# arm-mini-pro.net
KiCad netlist of a schematic drawn in EAGLE
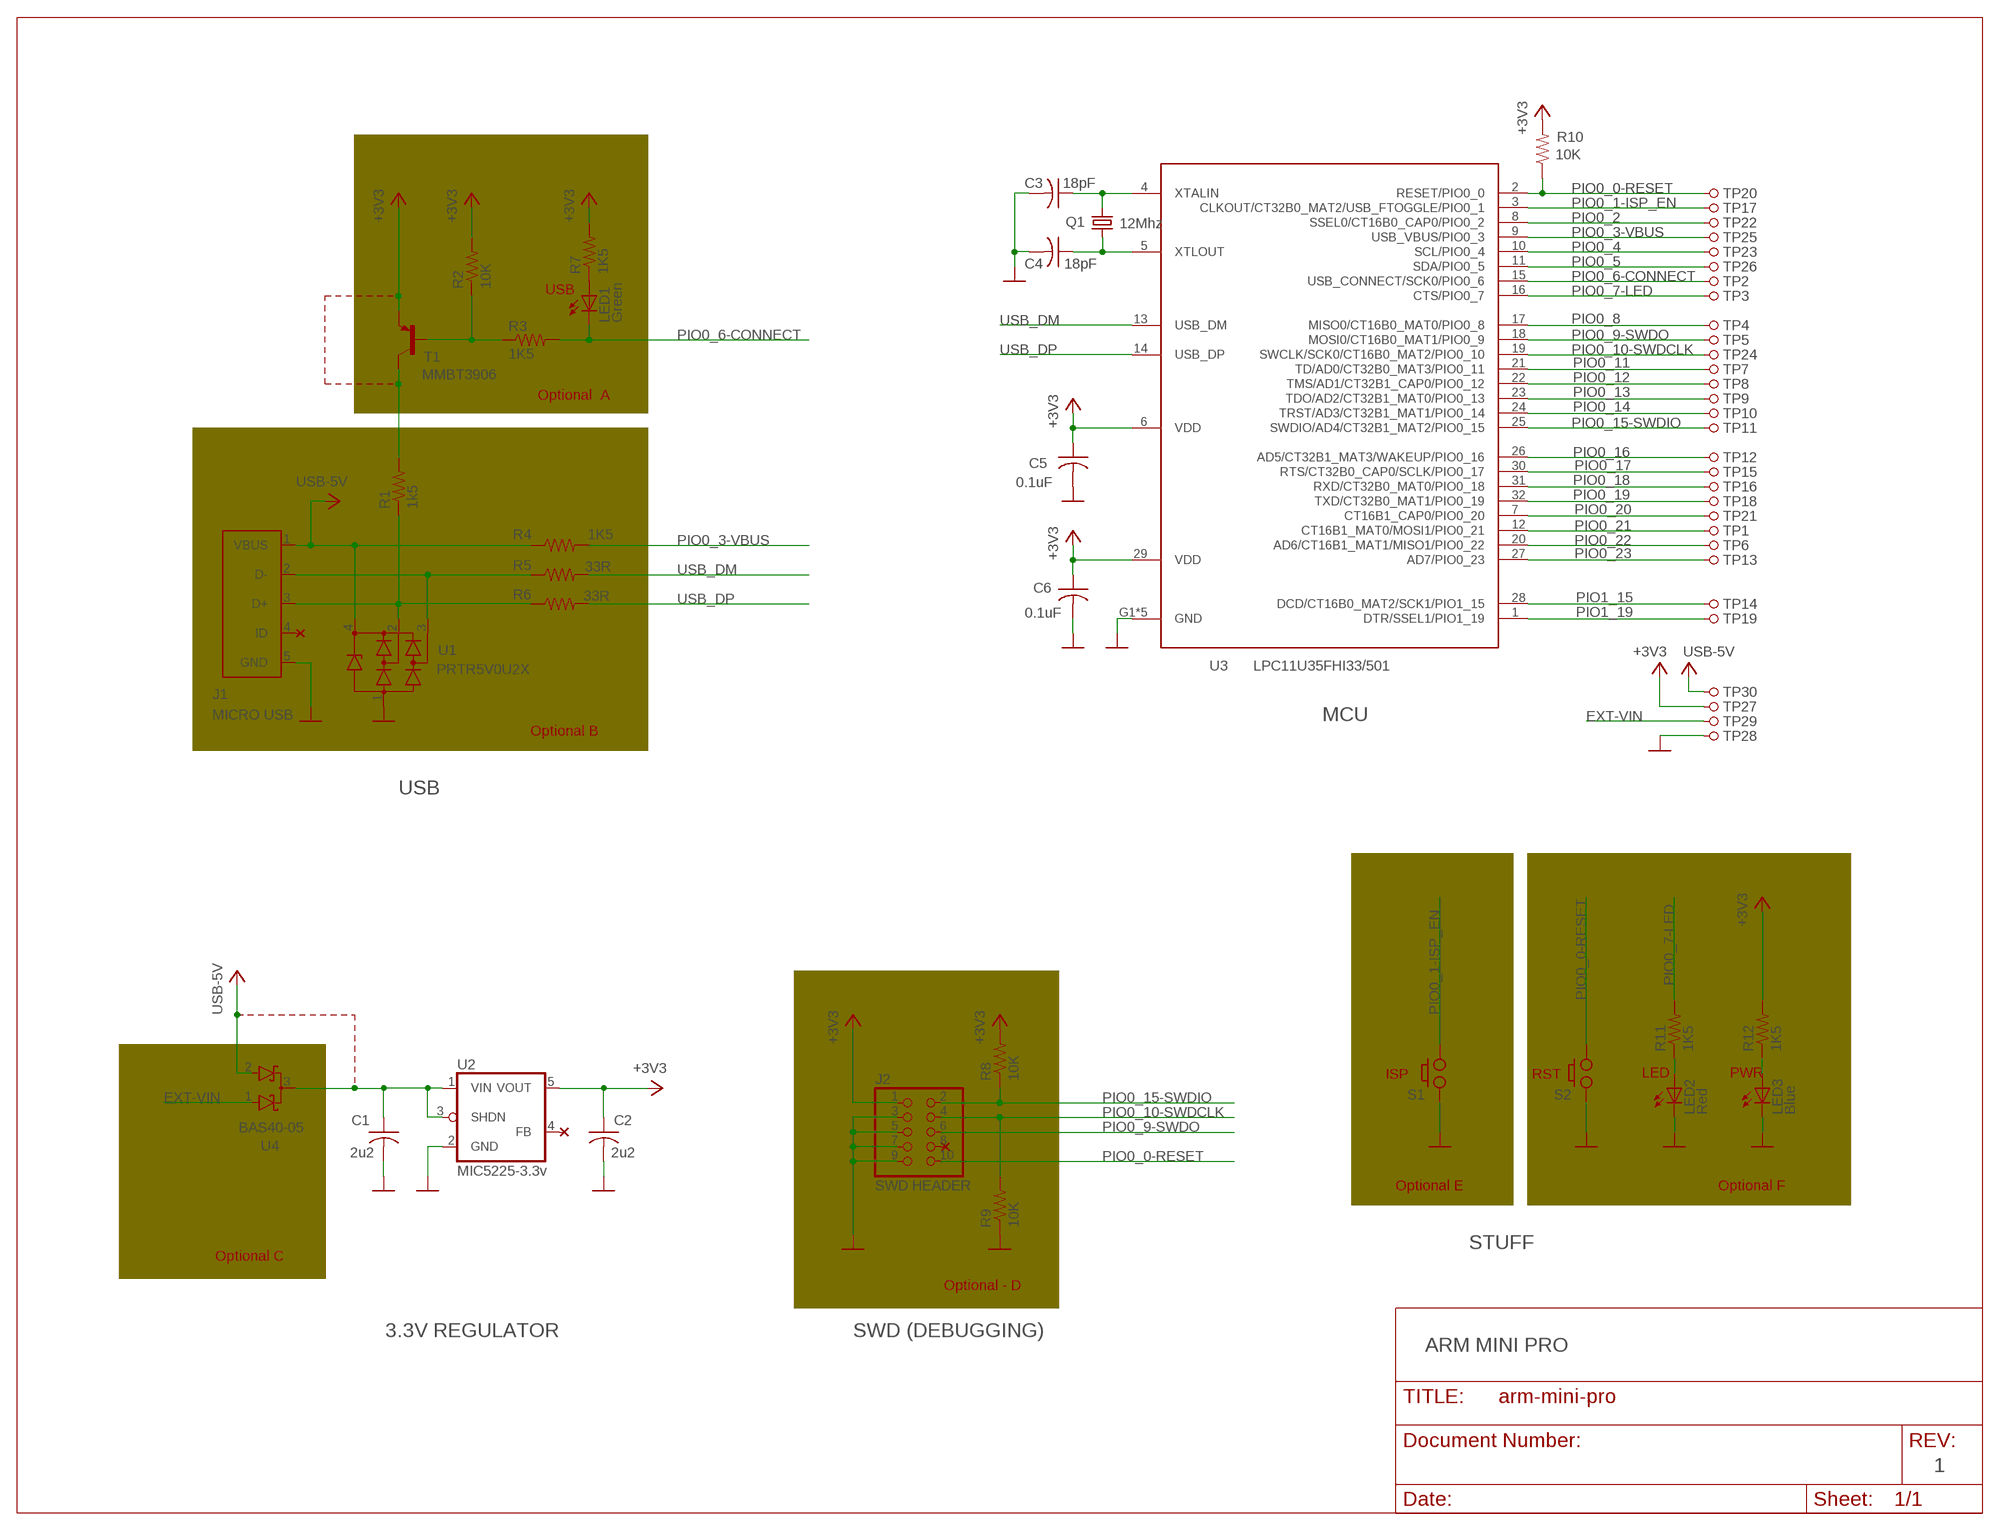
[diagram p0: schematic, sheet 1]

(export (version "E")
  (design (tool "Eeschema 10.0.6"))
  (components
    (comp (ref "C1")
      (value "2u2")
      (footprint "eagle-import:C0603K")
      (libsource (lib "eagle-import") (part "CAPACITORC0603K"))
    )
    (comp (ref "C2")
      (value "2u2")
      (footprint "eagle-import:C0603K")
      (libsource (lib "eagle-import") (part "CAPACITORC0603K"))
    )
    (comp (ref "C3")
      (value "18pF")
      (footprint "eagle-import:C0402K")
      (libsource (lib "eagle-import") (part "C-USC0402K"))
    )
    (comp (ref "C4")
      (value "18pF")
      (footprint "eagle-import:C0402K")
      (libsource (lib "eagle-import") (part "C-USC0402K"))
    )
    (comp (ref "C5")
      (value "0.1uF")
      (footprint "eagle-import:C0603K")
      (libsource (lib "eagle-import") (part "CAPACITORC0603K"))
    )
    (comp (ref "C6")
      (value "0.1uF")
      (footprint "eagle-import:C0603K")
      (libsource (lib "eagle-import") (part "CAPACITORC0603K"))
    )
    (comp (ref "J1")
      (value "MICRO USB")
      (footprint "eagle-import:USB-MICRO-ZX62RD-AB-5P8")
      (libsource (lib "eagle-import") (part "USB"))
    )
    (comp (ref "J2")
      (value "SWD HEADER")
      (footprint "eagle-import:SWD-HEADER")
      (libsource (lib "eagle-import") (part "SWD-HEADER"))
    )
    (comp (ref "LED1")
      (value "Green")
      (footprint "eagle-import:CHIP-LED0603")
      (libsource (lib "eagle-import") (part "LEDCHIP-LED0603"))
    )
    (comp (ref "LED2")
      (value "Red")
      (footprint "eagle-import:CHIP-LED0603")
      (libsource (lib "eagle-import") (part "LEDCHIP-LED0603"))
    )
    (comp (ref "LED3")
      (value "Blue")
      (footprint "eagle-import:CHIP-LED0603")
      (libsource (lib "eagle-import") (part "LEDCHIP-LED0603"))
    )
    (comp (ref "Q1")
      (value "12Mhz")
      (footprint "eagle-import:CRYSTAL")
      (libsource (lib "eagle-import") (part "CRYSTALCTS406"))
    )
    (comp (ref "R1")
      (value "1k5")
      (footprint "eagle-import:R0402")
      (libsource (lib "eagle-import") (part "R-US_R0402"))
    )
    (comp (ref "R2")
      (value "10K")
      (footprint "eagle-import:R0402")
      (libsource (lib "eagle-import") (part "R-US_R0402"))
    )
    (comp (ref "R3")
      (value "1K5")
      (footprint "eagle-import:R0402")
      (libsource (lib "eagle-import") (part "R-US_R0402"))
    )
    (comp (ref "R4")
      (value "1K5")
      (footprint "eagle-import:R0402")
      (libsource (lib "eagle-import") (part "R-US_R0402"))
    )
    (comp (ref "R5")
      (value "33R")
      (footprint "eagle-import:R0402")
      (libsource (lib "eagle-import") (part "R-US_R0402"))
    )
    (comp (ref "R6")
      (value "33R")
      (footprint "eagle-import:R0402")
      (libsource (lib "eagle-import") (part "R-US_R0402"))
    )
    (comp (ref "R7")
      (value "1K5")
      (footprint "eagle-import:R0402")
      (libsource (lib "eagle-import") (part "R-US_R0402"))
    )
    (comp (ref "R8")
      (value "10K")
      (footprint "eagle-import:R0402")
      (libsource (lib "eagle-import") (part "R-US_R0402"))
    )
    (comp (ref "R9")
      (value "10K")
      (footprint "eagle-import:R0402")
      (libsource (lib "eagle-import") (part "R-US_R0402"))
    )
    (comp (ref "R10")
      (value "10K")
      (footprint "eagle-import:R0402")
      (libsource (lib "eagle-import") (part "R-US_R0402"))
    )
    (comp (ref "R11")
      (value "1K5")
      (footprint "eagle-import:R0402")
      (libsource (lib "eagle-import") (part "R-US_R0402"))
    )
    (comp (ref "R12")
      (value "1K5")
      (footprint "eagle-import:R0402")
      (libsource (lib "eagle-import") (part "R-US_R0402"))
    )
    (comp (ref "S1")
      (value "PUSH_BUTTON")
      (footprint "eagle-import:PUSH_BUTTON")
      (libsource (lib "eagle-import") (part "PUSH_BUTTON"))
    )
    (comp (ref "S2")
      (value "PUSH_BUTTON")
      (footprint "eagle-import:PUSH_BUTTON")
      (libsource (lib "eagle-import") (part "PUSH_BUTTON"))
    )
    (comp (ref "T1")
      (value "MMBT3906")
      (footprint "eagle-import:SOT23-BEC")
      (libsource (lib "eagle-import") (part "-PNP-SOT23-BECBC857B"))
    )
    (comp (ref "TP1")
      (value "HDR1")
      (footprint "eagle-import:1X01-SQUARE")
      (libsource (lib "eagle-import") (part "PINHD-1X1SQUARE"))
    )
    (comp (ref "TP2")
      (value "HDR1")
      (footprint "eagle-import:1X01")
      (libsource (lib "eagle-import") (part "PINHD-1X1"))
    )
    (comp (ref "TP3")
      (value "HDR1")
      (footprint "eagle-import:1X01")
      (libsource (lib "eagle-import") (part "PINHD-1X1"))
    )
    (comp (ref "TP4")
      (value "HDR1")
      (footprint "eagle-import:1X01")
      (libsource (lib "eagle-import") (part "PINHD-1X1"))
    )
    (comp (ref "TP5")
      (value "HDR1")
      (footprint "eagle-import:1X01")
      (libsource (lib "eagle-import") (part "PINHD-1X1"))
    )
    (comp (ref "TP6")
      (value "HDR1")
      (footprint "eagle-import:1X01")
      (libsource (lib "eagle-import") (part "PINHD-1X1"))
    )
    (comp (ref "TP7")
      (value "HDR1")
      (footprint "eagle-import:1X01")
      (libsource (lib "eagle-import") (part "PINHD-1X1"))
    )
    (comp (ref "TP8")
      (value "HDR1")
      (footprint "eagle-import:1X01")
      (libsource (lib "eagle-import") (part "PINHD-1X1"))
    )
    (comp (ref "TP9")
      (value "HDR1")
      (footprint "eagle-import:1X01")
      (libsource (lib "eagle-import") (part "PINHD-1X1"))
    )
    (comp (ref "TP10")
      (value "HDR1")
      (footprint "eagle-import:1X01")
      (libsource (lib "eagle-import") (part "PINHD-1X1"))
    )
    (comp (ref "TP11")
      (value "HDR1")
      (footprint "eagle-import:1X01")
      (libsource (lib "eagle-import") (part "PINHD-1X1"))
    )
    (comp (ref "TP12")
      (value "HDR1")
      (footprint "eagle-import:1X01")
      (libsource (lib "eagle-import") (part "PINHD-1X1"))
    )
    (comp (ref "TP13")
      (value "HDR1")
      (footprint "eagle-import:1X01")
      (libsource (lib "eagle-import") (part "PINHD-1X1"))
    )
    (comp (ref "TP14")
      (value "HDR1")
      (footprint "eagle-import:1X01")
      (libsource (lib "eagle-import") (part "PINHD-1X1"))
    )
    (comp (ref "TP15")
      (value "HDR1")
      (footprint "eagle-import:1X01")
      (libsource (lib "eagle-import") (part "PINHD-1X1"))
    )
    (comp (ref "TP16")
      (value "HDR1")
      (footprint "eagle-import:1X01")
      (libsource (lib "eagle-import") (part "PINHD-1X1"))
    )
    (comp (ref "TP17")
      (value "HDR1")
      (footprint "eagle-import:1X01")
      (libsource (lib "eagle-import") (part "PINHD-1X1"))
    )
    (comp (ref "TP18")
      (value "HDR1")
      (footprint "eagle-import:1X01")
      (libsource (lib "eagle-import") (part "PINHD-1X1"))
    )
    (comp (ref "TP19")
      (value "HDR1")
      (footprint "eagle-import:1X01")
      (libsource (lib "eagle-import") (part "PINHD-1X1"))
    )
    (comp (ref "TP20")
      (value "HDR1")
      (footprint "eagle-import:1X01")
      (libsource (lib "eagle-import") (part "PINHD-1X1"))
    )
    (comp (ref "TP21")
      (value "HDR1")
      (footprint "eagle-import:1X01")
      (libsource (lib "eagle-import") (part "PINHD-1X1"))
    )
    (comp (ref "TP22")
      (value "HDR1")
      (footprint "eagle-import:1X01")
      (libsource (lib "eagle-import") (part "PINHD-1X1"))
    )
    (comp (ref "TP23")
      (value "HDR1")
      (footprint "eagle-import:1X01")
      (libsource (lib "eagle-import") (part "PINHD-1X1"))
    )
    (comp (ref "TP24")
      (value "HDR1")
      (footprint "eagle-import:1X01")
      (libsource (lib "eagle-import") (part "PINHD-1X1"))
    )
    (comp (ref "TP25")
      (value "HDR1")
      (footprint "eagle-import:1X01")
      (libsource (lib "eagle-import") (part "PINHD-1X1"))
    )
    (comp (ref "TP26")
      (value "HDR1")
      (footprint "eagle-import:1X01")
      (libsource (lib "eagle-import") (part "PINHD-1X1"))
    )
    (comp (ref "TP27")
      (value "HDR1")
      (footprint "eagle-import:1X01")
      (libsource (lib "eagle-import") (part "PINHD-1X1"))
    )
    (comp (ref "TP28")
      (value "HDR1")
      (footprint "eagle-import:1X01")
      (libsource (lib "eagle-import") (part "PINHD-1X1"))
    )
    (comp (ref "TP29")
      (value "HDR1")
      (footprint "eagle-import:1X01")
      (libsource (lib "eagle-import") (part "PINHD-1X1"))
    )
    (comp (ref "TP30")
      (value "HDR1")
      (footprint "eagle-import:1X01")
      (libsource (lib "eagle-import") (part "PINHD-1X1"))
    )
    (comp (ref "U1")
      (value "PRTR5V0U2X")
      (footprint "eagle-import:SOT143B")
      (libsource (lib "eagle-import") (part "PRTR5V0U2X"))
    )
    (comp (ref "U2")
      (value "MIC5225-3.3v")
      (footprint "eagle-import:SOT25")
      (libsource (lib "eagle-import") (part "TC1015"))
    )
    (comp (ref "U3")
      (value "LPC11U35FHI33/501")
      (footprint "eagle-import:HVQFN33-5MM")
      (libsource (lib "eagle-import") (part "LPC11U35FHN33/501"))
    )
    (comp (ref "U4")
      (value "BAS40-05")
      (footprint "eagle-import:SOT23")
      (libsource (lib "eagle-import") (part "BAS40-05"))
    )
  )
  (nets
    (net (code "1") (name "+3V3") (class "Default")
      (node (ref "C2") (pin "1") (pinfunction "1_1") (pintype "passive"))
      (node (ref "C5") (pin "1") (pinfunction "1_1") (pintype "passive"))
      (node (ref "C6") (pin "1") (pinfunction "1_1") (pintype "passive"))
      (node (ref "J2") (pin "1") (pinfunction "1_1") (pintype "passive"))
      (node (ref "R10") (pin "2") (pinfunction "2_2") (pintype "passive"))
      (node (ref "R12") (pin "2") (pinfunction "2_2") (pintype "passive"))
      (node (ref "R2") (pin "2") (pinfunction "2_2") (pintype "passive"))
      (node (ref "R7") (pin "2") (pinfunction "2_2") (pintype "passive"))
      (node (ref "R8") (pin "2") (pinfunction "2_2") (pintype "passive"))
      (node (ref "T1") (pin "E") (pinfunction "E_E") (pintype "passive"))
      (node (ref "TP27") (pin "1") (pinfunction "1_1") (pintype "passive"))
      (node (ref "U2") (pin "5") (pinfunction "VOUT_5") (pintype "power_in"))
      (node (ref "U3") (pin "29") (pinfunction "VDD_29") (pintype "bidirectional"))
      (node (ref "U3") (pin "6") (pinfunction "VDD_6") (pintype "bidirectional"))
    )
    (net (code "2") (name "/EXT-VIN") (class "Default")
      (node (ref "TP29") (pin "1") (pinfunction "1_1") (pintype "passive"))
      (node (ref "U4") (pin "1") (pinfunction "A1_1") (pintype "passive"))
    )
    (net (code "3") (name "/PIO0_0-RESET") (class "Default")
      (node (ref "J2") (pin "10") (pinfunction "10_10") (pintype "passive"))
      (node (ref "R10") (pin "1") (pinfunction "1_1") (pintype "passive"))
      (node (ref "S2") (pin "B2") (pinfunction "2_B2") (pintype "passive"))
      (node (ref "TP20") (pin "1") (pinfunction "1_1") (pintype "passive"))
      (node (ref "U3") (pin "2") (pinfunction "RESET/PIO0_0_2") (pintype "bidirectional"))
    )
    (net (code "4") (name "/PIO0_1-ISP_EN") (class "Default")
      (node (ref "S1") (pin "B2") (pinfunction "2_B2") (pintype "passive"))
      (node (ref "TP17") (pin "1") (pinfunction "1_1") (pintype "passive"))
      (node (ref "U3") (pin "3") (pinfunction "CLKOUT/CT32B0_MAT2/USB_FTOGGLE/PIO0_1_3") (pintype "bidirectional"))
    )
    (net (code "5") (name "/PIO0_2") (class "Default")
      (node (ref "TP22") (pin "1") (pinfunction "1_1") (pintype "passive"))
      (node (ref "U3") (pin "8") (pinfunction "SSEL0/CT16B0_CAP0/PIO0_2_8") (pintype "bidirectional"))
    )
    (net (code "6") (name "/PIO0_3-VBUS") (class "Default")
      (node (ref "R4") (pin "2") (pinfunction "2_2") (pintype "passive"))
      (node (ref "TP25") (pin "1") (pinfunction "1_1") (pintype "passive"))
      (node (ref "U3") (pin "9") (pinfunction "USB_VBUS/PIO0_3_9") (pintype "bidirectional"))
    )
    (net (code "7") (name "/PIO0_4") (class "Default")
      (node (ref "TP23") (pin "1") (pinfunction "1_1") (pintype "passive"))
      (node (ref "U3") (pin "10") (pinfunction "SCL/PIO0_4_10") (pintype "bidirectional"))
    )
    (net (code "8") (name "/PIO0_5") (class "Default")
      (node (ref "TP26") (pin "1") (pinfunction "1_1") (pintype "passive"))
      (node (ref "U3") (pin "11") (pinfunction "SDA/PIO0_5_11") (pintype "bidirectional"))
    )
    (net (code "9") (name "/PIO0_6-CONNECT") (class "Default")
      (node (ref "LED1") (pin "C") (pinfunction "C_C") (pintype "passive"))
      (node (ref "R3") (pin "2") (pinfunction "2_2") (pintype "passive"))
      (node (ref "TP2") (pin "1") (pinfunction "1_1") (pintype "passive"))
      (node (ref "U3") (pin "15") (pinfunction "USB_CONNECT/SCK0/PIO0_6_15") (pintype "bidirectional"))
    )
    (net (code "10") (name "/PIO0_7-LED") (class "Default")
      (node (ref "R11") (pin "2") (pinfunction "2_2") (pintype "passive"))
      (node (ref "TP3") (pin "1") (pinfunction "1_1") (pintype "passive"))
      (node (ref "U3") (pin "16") (pinfunction "CTS/PIO0_7_16") (pintype "bidirectional"))
    )
    (net (code "11") (name "/PIO0_8") (class "Default")
      (node (ref "TP4") (pin "1") (pinfunction "1_1") (pintype "passive"))
      (node (ref "U3") (pin "17") (pinfunction "MISO0/CT16B0_MAT0/PIO0_8_17") (pintype "bidirectional"))
    )
    (net (code "12") (name "/PIO0_9-SWDO") (class "Default")
      (node (ref "J2") (pin "6") (pinfunction "6_6") (pintype "passive"))
      (node (ref "TP5") (pin "1") (pinfunction "1_1") (pintype "passive"))
      (node (ref "U3") (pin "18") (pinfunction "MOSI0/CT16B0_MAT1/PIO0_9_18") (pintype "bidirectional"))
    )
    (net (code "13") (name "/PIO0_10-SWDCLK") (class "Default")
      (node (ref "J2") (pin "4") (pinfunction "4_4") (pintype "passive"))
      (node (ref "R9") (pin "2") (pinfunction "2_2") (pintype "passive"))
      (node (ref "TP24") (pin "1") (pinfunction "1_1") (pintype "passive"))
      (node (ref "U3") (pin "19") (pinfunction "SWCLK/SCK0/CT16B0_MAT2/PIO0_10_19") (pintype "bidirectional"))
    )
    (net (code "14") (name "/PIO0_11") (class "Default")
      (node (ref "TP7") (pin "1") (pinfunction "1_1") (pintype "passive"))
      (node (ref "U3") (pin "21") (pinfunction "TD/AD0/CT32B0_MAT3/PIO0_11_21") (pintype "bidirectional"))
    )
    (net (code "15") (name "/PIO0_12") (class "Default")
      (node (ref "TP8") (pin "1") (pinfunction "1_1") (pintype "passive"))
      (node (ref "U3") (pin "22") (pinfunction "TMS/AD1/CT32B1_CAP0/PIO0_12_22") (pintype "bidirectional"))
    )
    (net (code "16") (name "/PIO0_13") (class "Default")
      (node (ref "TP9") (pin "1") (pinfunction "1_1") (pintype "passive"))
      (node (ref "U3") (pin "23") (pinfunction "TDO/AD2/CT32B1_MAT0/PIO0_13_23") (pintype "bidirectional"))
    )
    (net (code "17") (name "/PIO0_14") (class "Default")
      (node (ref "TP10") (pin "1") (pinfunction "1_1") (pintype "passive"))
      (node (ref "U3") (pin "24") (pinfunction "TRST/AD3/CT32B1_MAT1/PIO0_14_24") (pintype "bidirectional"))
    )
    (net (code "18") (name "/PIO0_15-SWDIO") (class "Default")
      (node (ref "J2") (pin "2") (pinfunction "2_2") (pintype "passive"))
      (node (ref "R8") (pin "1") (pinfunction "1_1") (pintype "passive"))
      (node (ref "TP11") (pin "1") (pinfunction "1_1") (pintype "passive"))
      (node (ref "U3") (pin "25") (pinfunction "SWDIO/AD4/CT32B1_MAT2/PIO0_15_25") (pintype "bidirectional"))
    )
    (net (code "19") (name "/PIO0_16") (class "Default")
      (node (ref "TP12") (pin "1") (pinfunction "1_1") (pintype "passive"))
      (node (ref "U3") (pin "26") (pinfunction "AD5/CT32B1_MAT3/WAKEUP/PIO0_16_26") (pintype "bidirectional"))
    )
    (net (code "20") (name "/PIO0_17") (class "Default")
      (node (ref "TP15") (pin "1") (pinfunction "1_1") (pintype "passive"))
      (node (ref "U3") (pin "30") (pinfunction "RTS/CT32B0_CAP0/SCLK/PIO0_17_30") (pintype "bidirectional"))
    )
    (net (code "21") (name "/PIO0_18") (class "Default")
      (node (ref "TP16") (pin "1") (pinfunction "1_1") (pintype "passive"))
      (node (ref "U3") (pin "31") (pinfunction "RXD/CT32B0_MAT0/PIO0_18_31") (pintype "bidirectional"))
    )
    (net (code "22") (name "/PIO0_19") (class "Default")
      (node (ref "TP18") (pin "1") (pinfunction "1_1") (pintype "passive"))
      (node (ref "U3") (pin "32") (pinfunction "TXD/CT32B0_MAT1/PIO0_19_32") (pintype "bidirectional"))
    )
    (net (code "23") (name "/PIO0_20") (class "Default")
      (node (ref "TP21") (pin "1") (pinfunction "1_1") (pintype "passive"))
      (node (ref "U3") (pin "7") (pinfunction "CT16B1_CAP0/PIO0_20_7") (pintype "bidirectional"))
    )
    (net (code "24") (name "/PIO0_21") (class "Default")
      (node (ref "TP1") (pin "1") (pinfunction "1_1") (pintype "passive"))
      (node (ref "U3") (pin "12") (pinfunction "CT16B1_MAT0/MOSI1/PIO0_21_12") (pintype "bidirectional"))
    )
    (net (code "25") (name "/PIO0_22") (class "Default")
      (node (ref "TP6") (pin "1") (pinfunction "1_1") (pintype "passive"))
      (node (ref "U3") (pin "20") (pinfunction "AD6/CT16B1_MAT1/MISO1/PIO0_22_20") (pintype "bidirectional"))
    )
    (net (code "26") (name "/PIO0_23") (class "Default")
      (node (ref "TP13") (pin "1") (pinfunction "1_1") (pintype "passive"))
      (node (ref "U3") (pin "27") (pinfunction "AD7/PIO0_23_27") (pintype "bidirectional"))
    )
    (net (code "27") (name "/PIO1_15") (class "Default")
      (node (ref "TP14") (pin "1") (pinfunction "1_1") (pintype "passive"))
      (node (ref "U3") (pin "28") (pinfunction "DCD/CT16B0_MAT2/SCK1/PIO1_15_28") (pintype "bidirectional"))
    )
    (net (code "28") (name "/PIO1_19") (class "Default")
      (node (ref "TP19") (pin "1") (pinfunction "1_1") (pintype "passive"))
      (node (ref "U3") (pin "1") (pinfunction "DTR/SSEL1/PIO1_19_1") (pintype "bidirectional"))
    )
    (net (code "29") (name "/USB_DM") (class "Default")
      (node (ref "R5") (pin "2") (pinfunction "2_2") (pintype "passive"))
      (node (ref "U3") (pin "13") (pinfunction "USB_DM_13") (pintype "bidirectional"))
    )
    (net (code "30") (name "/USB_DP") (class "Default")
      (node (ref "R6") (pin "2") (pinfunction "2_2") (pintype "passive"))
      (node (ref "U3") (pin "14") (pinfunction "USB_DP_14") (pintype "bidirectional"))
    )
    (net (code "31") (name "GND") (class "Default")
      (node (ref "C1") (pin "2") (pinfunction "2_2") (pintype "passive"))
      (node (ref "C2") (pin "2") (pinfunction "2_2") (pintype "passive"))
      (node (ref "C3") (pin "2") (pinfunction "2_2") (pintype "passive"))
      (node (ref "C4") (pin "2") (pinfunction "2_2") (pintype "passive"))
      (node (ref "C5") (pin "2") (pinfunction "2_2") (pintype "passive"))
      (node (ref "C6") (pin "2") (pinfunction "2_2") (pintype "passive"))
      (node (ref "J1") (pin "5") (pinfunction "GND_5") (pintype "bidirectional"))
      (node (ref "J2") (pin "3") (pinfunction "3_3") (pintype "passive"))
      (node (ref "J2") (pin "5") (pinfunction "5_5") (pintype "passive"))
      (node (ref "J2") (pin "7") (pinfunction "7_7") (pintype "passive"))
      (node (ref "J2") (pin "9") (pinfunction "9_9") (pintype "passive"))
      (node (ref "LED2") (pin "C") (pinfunction "C_C") (pintype "passive"))
      (node (ref "LED3") (pin "C") (pinfunction "C_C") (pintype "passive"))
      (node (ref "R9") (pin "1") (pinfunction "1_1") (pintype "passive"))
      (node (ref "S1") (pin "A1") (pinfunction "1_A1") (pintype "passive"))
      (node (ref "S2") (pin "A1") (pinfunction "1_A1") (pintype "passive"))
      (node (ref "TP28") (pin "1") (pinfunction "1_1") (pintype "passive"))
      (node (ref "U1") (pin "1") (pinfunction "GND_1") (pintype "passive"))
      (node (ref "U2") (pin "2") (pinfunction "GND_2") (pintype "power_in"))
      (node (ref "U3") (pin "G1") (pinfunction "GND_G1") (pintype "bidirectional"))
      (node (ref "U3") (pin "G2") (pinfunction "GND_G2") (pintype "bidirectional"))
      (node (ref "U3") (pin "G3") (pinfunction "GND_G3") (pintype "bidirectional"))
      (node (ref "U3") (pin "G4") (pinfunction "GND_G4") (pintype "bidirectional"))
      (node (ref "U3") (pin "TAB") (pinfunction "GND_TAB") (pintype "bidirectional"))
    )
    (net (code "32") (name "Net-(J1-D+)") (class "Default")
      (node (ref "J1") (pin "3") (pinfunction "D+_3") (pintype "bidirectional"))
      (node (ref "R1") (pin "1") (pinfunction "1_1") (pintype "passive"))
      (node (ref "R6") (pin "1") (pinfunction "1_1") (pintype "passive"))
      (node (ref "U1") (pin "2") (pinfunction "IO1_2") (pintype "passive"))
    )
    (net (code "33") (name "Net-(J1-D-)") (class "Default")
      (node (ref "J1") (pin "2") (pinfunction "D-_2") (pintype "bidirectional"))
      (node (ref "R5") (pin "1") (pinfunction "1_1") (pintype "passive"))
      (node (ref "U1") (pin "3") (pinfunction "IO2_3") (pintype "passive"))
    )
    (net (code "34") (name "Net-(LED1-PadA)") (class "Default")
      (node (ref "LED1") (pin "A") (pinfunction "A_A") (pintype "passive"))
      (node (ref "R7") (pin "1") (pinfunction "1_1") (pintype "passive"))
    )
    (net (code "35") (name "Net-(LED2-PadA)") (class "Default")
      (node (ref "LED2") (pin "A") (pinfunction "A_A") (pintype "passive"))
      (node (ref "R11") (pin "1") (pinfunction "1_1") (pintype "passive"))
    )
    (net (code "36") (name "Net-(LED3-PadA)") (class "Default")
      (node (ref "LED3") (pin "A") (pinfunction "A_A") (pintype "passive"))
      (node (ref "R12") (pin "1") (pinfunction "1_1") (pintype "passive"))
    )
    (net (code "37") (name "Net-(Q1-2)") (class "Default")
      (node (ref "C3") (pin "1") (pinfunction "1_1") (pintype "passive"))
      (node (ref "Q1") (pin "3") (pinfunction "2_3") (pintype "passive"))
      (node (ref "U3") (pin "4") (pinfunction "XTALIN_4") (pintype "bidirectional"))
    )
    (net (code "38") (name "Net-(R1-Pad2)") (class "Default")
      (node (ref "R1") (pin "2") (pinfunction "2_2") (pintype "passive"))
      (node (ref "T1") (pin "C") (pinfunction "C_C") (pintype "passive"))
    )
    (net (code "39") (name "Net-(R2-Pad1)") (class "Default")
      (node (ref "R2") (pin "1") (pinfunction "1_1") (pintype "passive"))
      (node (ref "R3") (pin "1") (pinfunction "1_1") (pintype "passive"))
      (node (ref "T1") (pin "B") (pinfunction "B_B") (pintype "passive"))
    )
    (net (code "40") (name "Net-(U2-SHDN)") (class "Default")
      (node (ref "C1") (pin "1") (pinfunction "1_1") (pintype "passive"))
      (node (ref "U2") (pin "1") (pinfunction "VIN_1") (pintype "power_in"))
      (node (ref "U2") (pin "3") (pinfunction "SHDN_3") (pintype "input"))
      (node (ref "U4") (pin "3") (pinfunction "C_3") (pintype "passive"))
    )
    (net (code "41") (name "Net-(U3-XTLOUT)") (class "Default")
      (node (ref "C4") (pin "1") (pinfunction "1_1") (pintype "passive"))
      (node (ref "Q1") (pin "1") (pinfunction "1_1") (pintype "passive"))
      (node (ref "U3") (pin "5") (pinfunction "XTLOUT_5") (pintype "bidirectional"))
    )
    (net (code "42") (name "USB-5V") (class "Default")
      (node (ref "J1") (pin "1") (pinfunction "VBUS_1") (pintype "bidirectional"))
      (node (ref "R4") (pin "1") (pinfunction "1_1") (pintype "passive"))
      (node (ref "TP30") (pin "1") (pinfunction "1_1") (pintype "passive"))
      (node (ref "U1") (pin "4") (pinfunction "VCC_4") (pintype "passive"))
      (node (ref "U4") (pin "2") (pinfunction "A2_2") (pintype "passive"))
    )
    (net (code "43") (name "unconnected-(J1-ID-Pad4)") (class "Default")
      (node (ref "J1") (pin "4") (pinfunction "ID_4") (pintype "bidirectional"))
    )
    (net (code "44") (name "unconnected-(J2-Pad8)") (class "Default")
      (node (ref "J2") (pin "8") (pinfunction "8_8") (pintype "passive"))
    )
    (net (code "45") (name "unconnected-(U2-FB-Pad4)") (class "Default")
      (node (ref "U2") (pin "4") (pinfunction "FB_4") (pintype "input"))
    )
  )
)
